# 03A-001.net
KiCad netlist of a schematic drawn in EAGLE
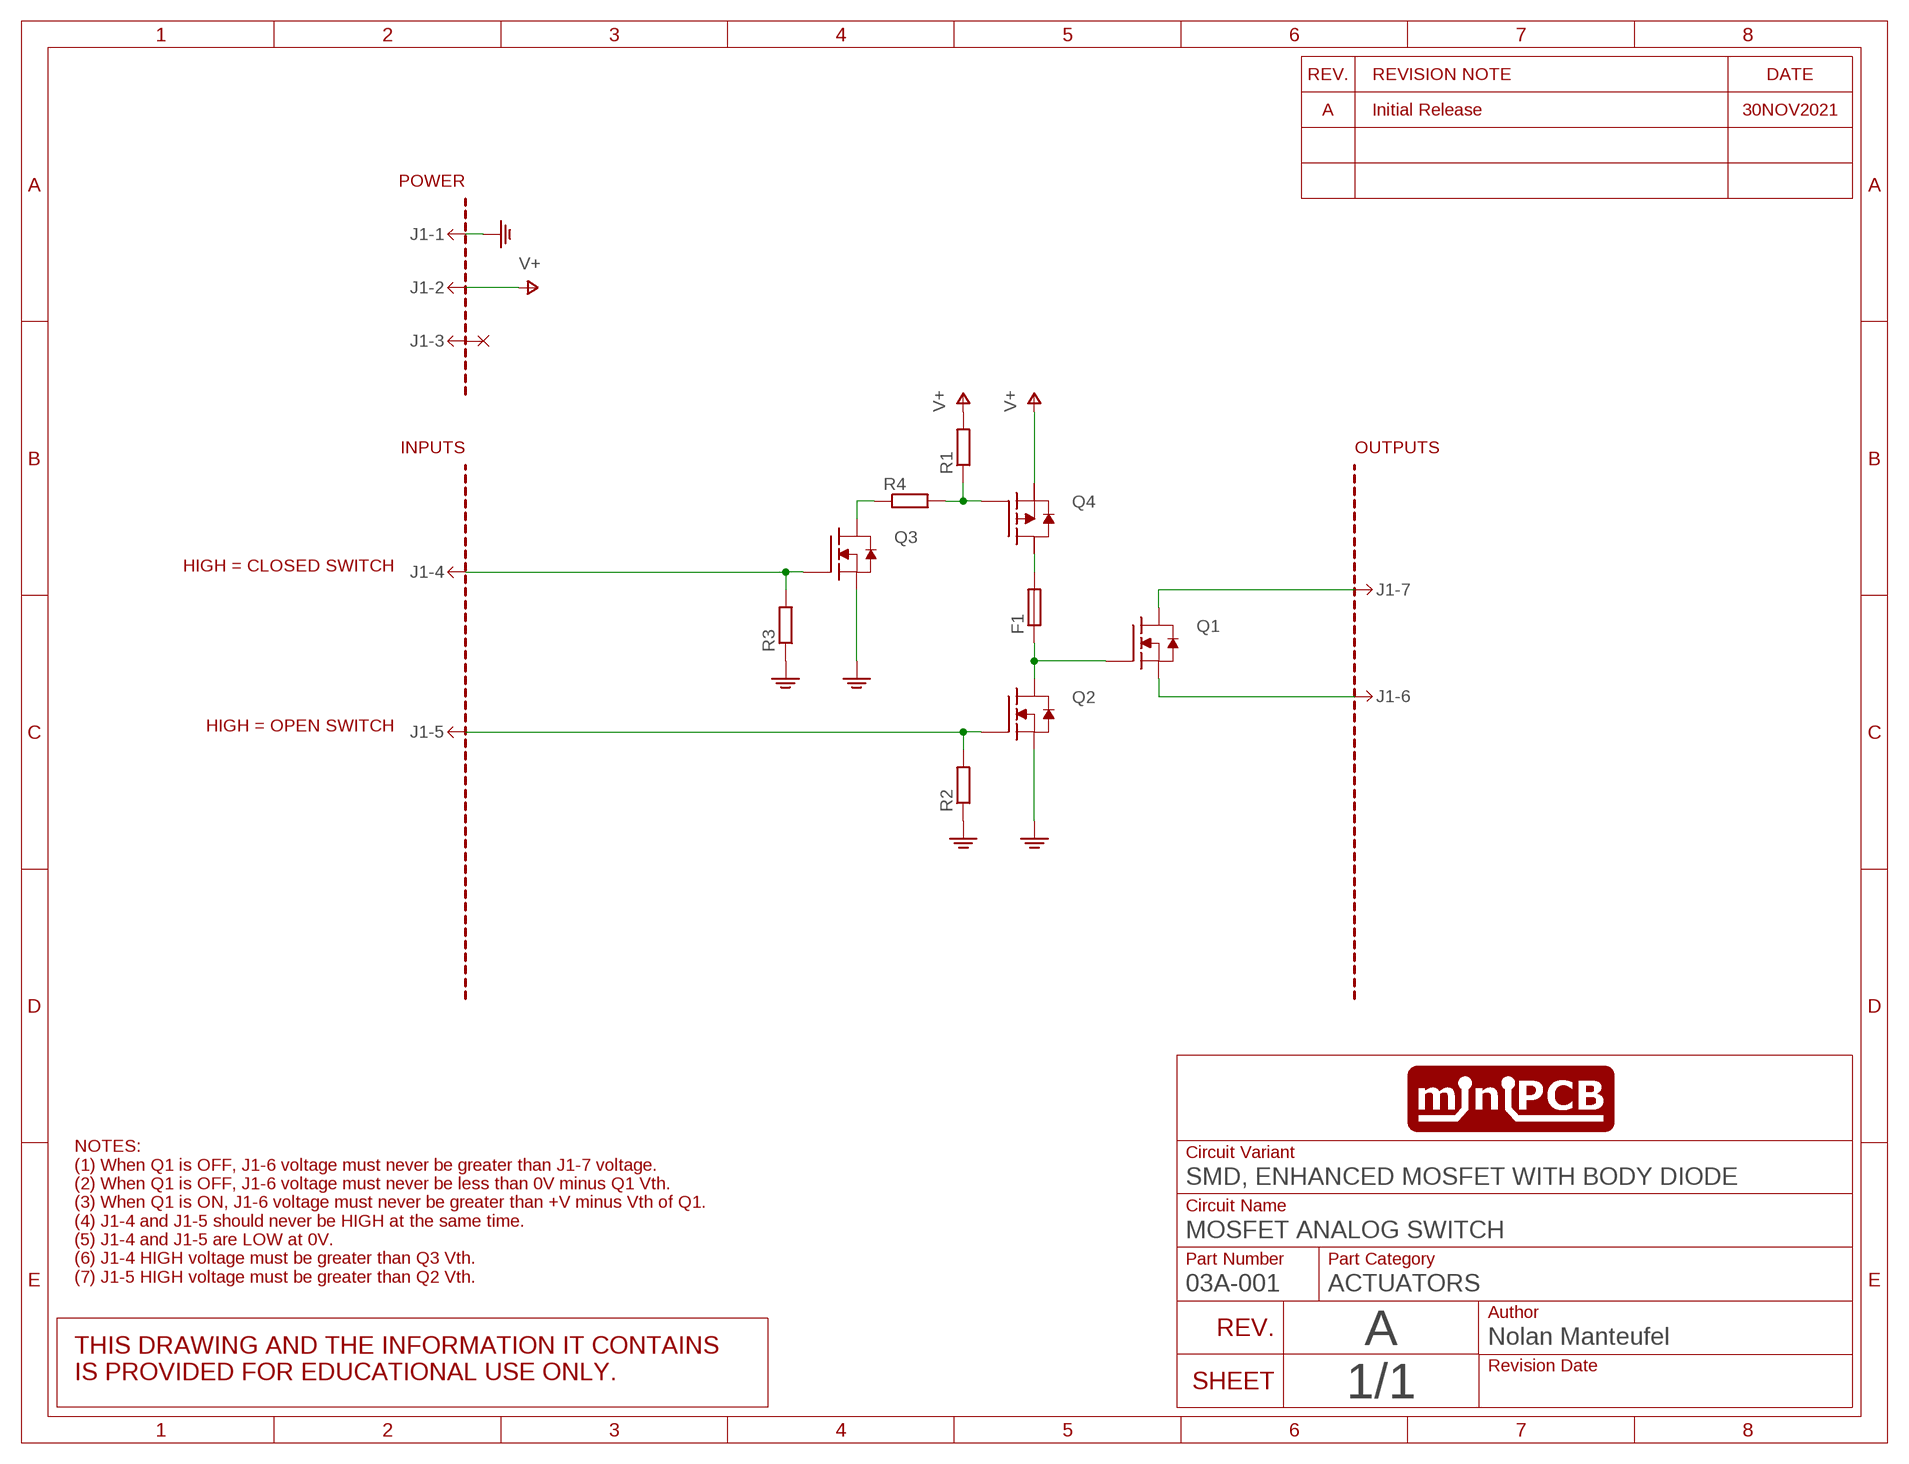
[diagram p0: schematic, sheet 1]

(export (version "E")
  (design (tool "Eeschema 10.0.6"))
  (components
    (comp (ref "F1")
      (value "FUSE0805")
      (footprint "eagle-import:F0805")
      (libsource (lib "eagle-import") (part "FUSE0805"))
    )
    (comp (ref "J1-")
      (value "MINIPCB_7P25")
      (footprint "eagle-import:MINIPCB_7P_25X25MM")
      (libsource (lib "eagle-import") (part "MINIPCB_7P25"))
    )
    (comp (ref "Q1")
      (value "MOSFET-NSOT23")
      (footprint "eagle-import:SOT23")
      (libsource (lib "eagle-import") (part "MOSFET-NSOT23"))
    )
    (comp (ref "Q2")
      (value "MOSFET-NSOT23")
      (footprint "eagle-import:SOT23")
      (libsource (lib "eagle-import") (part "MOSFET-NSOT23"))
    )
    (comp (ref "Q3")
      (value "MOSFET-NSOT23")
      (footprint "eagle-import:SOT23")
      (libsource (lib "eagle-import") (part "MOSFET-NSOT23"))
    )
    (comp (ref "Q4")
      (value "MOSFET-PNTR2101PT1G")
      (footprint "eagle-import:SOT23")
      (libsource (lib "eagle-import") (part "MOSFET-PNTR2101PT1G"))
    )
    (comp (ref "R1")
      (value "RESISTORSMD")
      (footprint "eagle-import:R0805")
      (libsource (lib "eagle-import") (part "RESISTORSMD"))
    )
    (comp (ref "R2")
      (value "RESISTORSMD")
      (footprint "eagle-import:R0805")
      (libsource (lib "eagle-import") (part "RESISTORSMD"))
    )
    (comp (ref "R3")
      (value "RESISTORSMD")
      (footprint "eagle-import:R0805")
      (libsource (lib "eagle-import") (part "RESISTORSMD"))
    )
    (comp (ref "R4")
      (value "RESISTORSMD")
      (footprint "eagle-import:R0805")
      (libsource (lib "eagle-import") (part "RESISTORSMD"))
    )
  )
  (nets
    (net (code "1") (name "GND") (class "Default")
      (node (ref "J1-") (pin "1") (pinfunction "1_1") (pintype "bidirectional"))
      (node (ref "Q2") (pin "2") (pinfunction "S_2") (pintype "passive"))
      (node (ref "Q3") (pin "2") (pinfunction "S_2") (pintype "passive"))
      (node (ref "R2") (pin "1") (pinfunction "1_1") (pintype "passive"))
      (node (ref "R3") (pin "1") (pinfunction "1_1") (pintype "passive"))
    )
    (net (code "2") (name "Net-(J1-D-1)") (class "Default")
      (node (ref "J1-") (pin "4") (pinfunction "1_4") (pintype "bidirectional"))
      (node (ref "Q3") (pin "1") (pinfunction "G_1") (pintype "passive"))
      (node (ref "R3") (pin "2") (pinfunction "2_2") (pintype "passive"))
    )
    (net (code "3") (name "Net-(J1-E-1)") (class "Default")
      (node (ref "J1-") (pin "5") (pinfunction "1_5") (pintype "bidirectional"))
      (node (ref "Q2") (pin "1") (pinfunction "G_1") (pintype "passive"))
      (node (ref "R2") (pin "2") (pinfunction "2_2") (pintype "passive"))
    )
    (net (code "4") (name "Net-(J1-F-1)") (class "Default")
      (node (ref "J1-") (pin "6") (pinfunction "1_6") (pintype "bidirectional"))
      (node (ref "Q1") (pin "2") (pinfunction "S_2") (pintype "passive"))
    )
    (net (code "5") (name "Net-(J1-G-1)") (class "Default")
      (node (ref "J1-") (pin "7") (pinfunction "1_7") (pintype "bidirectional"))
      (node (ref "Q1") (pin "3") (pinfunction "D_3") (pintype "passive"))
    )
    (net (code "6") (name "Net-(Q1-G)") (class "Default")
      (node (ref "F1") (pin "1") (pinfunction "1_1") (pintype "passive"))
      (node (ref "Q1") (pin "1") (pinfunction "G_1") (pintype "passive"))
      (node (ref "Q2") (pin "3") (pinfunction "D_3") (pintype "passive"))
    )
    (net (code "7") (name "Net-(Q3-D)") (class "Default")
      (node (ref "Q3") (pin "3") (pinfunction "D_3") (pintype "passive"))
      (node (ref "R4") (pin "1") (pinfunction "1_1") (pintype "passive"))
    )
    (net (code "8") (name "Net-(Q4-D)") (class "Default")
      (node (ref "F1") (pin "2") (pinfunction "2_2") (pintype "passive"))
      (node (ref "Q4") (pin "2") (pinfunction "D_2") (pintype "passive"))
    )
    (net (code "9") (name "Net-(Q4-G)") (class "Default")
      (node (ref "Q4") (pin "1") (pinfunction "G_1") (pintype "passive"))
      (node (ref "R1") (pin "1") (pinfunction "1_1") (pintype "passive"))
      (node (ref "R4") (pin "2") (pinfunction "2_2") (pintype "passive"))
    )
    (net (code "10") (name "V+") (class "Default")
      (node (ref "J1-") (pin "2") (pinfunction "1_2") (pintype "bidirectional"))
      (node (ref "Q4") (pin "3") (pinfunction "S_3") (pintype "passive"))
      (node (ref "R1") (pin "2") (pinfunction "2_2") (pintype "passive"))
    )
    (net (code "11") (name "unconnected-(J1-C-1-Pad3)") (class "Default")
      (node (ref "J1-") (pin "3") (pinfunction "1_3") (pintype "bidirectional"))
    )
  )
)
